# logoi_smd_gndpln_v0_1.net
KiCad netlist of a schematic drawn in EAGLE
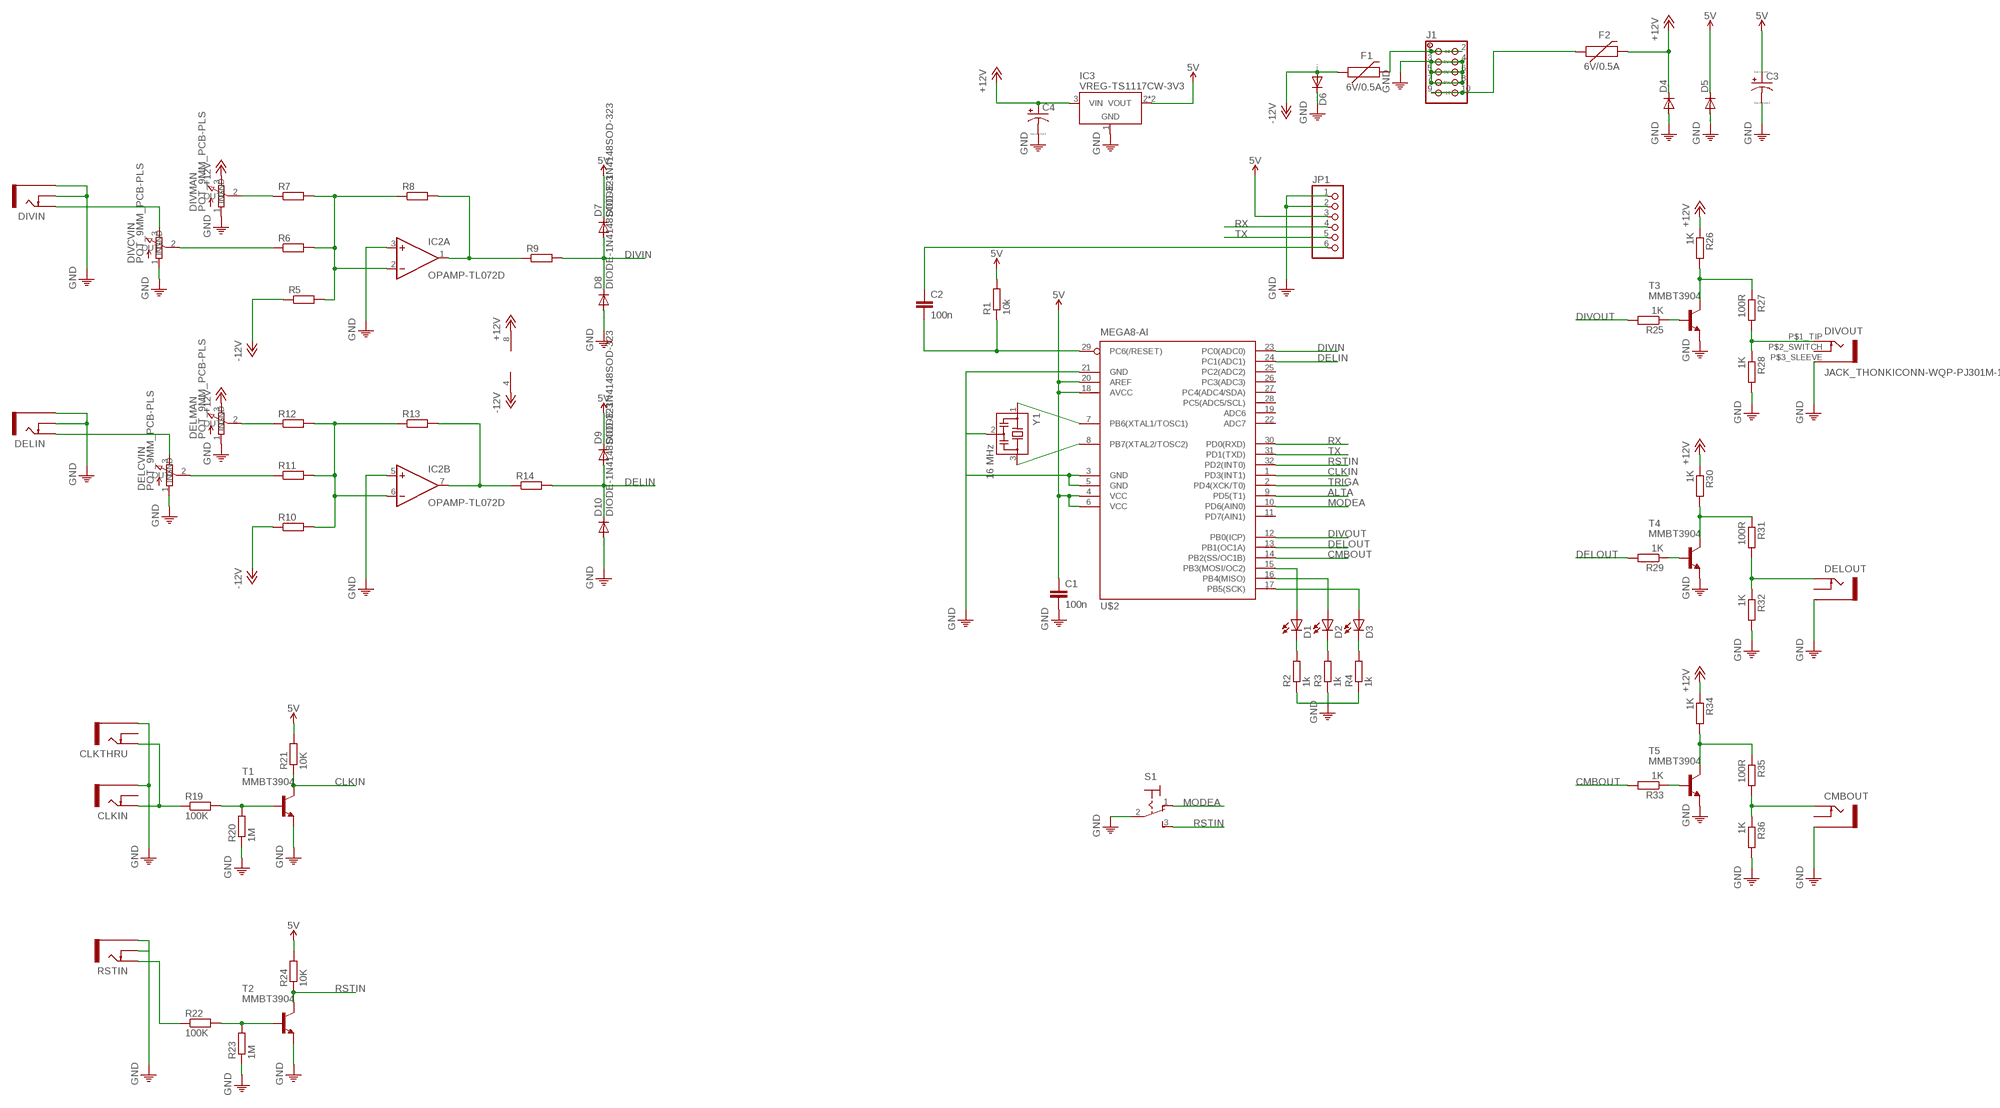
[diagram p0: schematic, sheet 1]

(export (version "E")
  (design (tool "Eeschema 10.0.6"))
  (components
    (comp (ref "C1")
      (value "100n")
      (footprint "eagle-import:C0603K")
      (libsource (lib "eagle-import") (part "CAPACITOR-EUC0603K"))
    )
    (comp (ref "C2")
      (value "100n")
      (footprint "eagle-import:C0603K")
      (libsource (lib "eagle-import") (part "CAPACITOR-EUC0603K"))
    )
    (comp (ref "C3")
      (value "CAPACITOR_POLARIZED-USE2.5-5")
      (footprint "eagle-import:E2,5-5")
      (libsource (lib "eagle-import") (part "CAPACITOR_POLARIZED-USE2.5-5"))
    )
    (comp (ref "C4")
      (value "CAPACITOR_POLARIZED-USE2.5-5")
      (footprint "eagle-import:E2,5-5")
      (libsource (lib "eagle-import") (part "CAPACITOR_POLARIZED-USE2.5-5"))
    )
    (comp (ref "CLKIN")
      (value "JACK_THONKICONNNEW")
      (footprint "eagle-import:WQP-PJ301M-12_JACK")
      (libsource (lib "eagle-import") (part "JACK_THONKICONNNEW"))
    )
    (comp (ref "CLKTHRU")
      (value "JACK_THONKICONNNEW")
      (footprint "eagle-import:WQP-PJ301M-12_JACK")
      (libsource (lib "eagle-import") (part "JACK_THONKICONNNEW"))
    )
    (comp (ref "CMBOUT")
      (value "JACK_THONKICONNNEW")
      (footprint "eagle-import:WQP-PJ301M-12_JACK")
      (libsource (lib "eagle-import") (part "JACK_THONKICONNNEW"))
    )
    (comp (ref "D1")
      (value "LED3MM")
      (footprint "eagle-import:LED3MM")
      (libsource (lib "eagle-import") (part "LED3MM"))
    )
    (comp (ref "D2")
      (value "LED3MM")
      (footprint "eagle-import:LED3MM")
      (libsource (lib "eagle-import") (part "LED3MM"))
    )
    (comp (ref "D3")
      (value "LED3MM")
      (footprint "eagle-import:LED3MM")
      (libsource (lib "eagle-import") (part "LED3MM"))
    )
    (comp (ref "D4")
      (value "DIODE-DO-214AC")
      (footprint "eagle-import:DO-214AC")
      (libsource (lib "eagle-import") (part "DIODE-DO-214AC"))
    )
    (comp (ref "D5")
      (value "DIODE-DO-214AC")
      (footprint "eagle-import:DO-214AC")
      (libsource (lib "eagle-import") (part "DIODE-DO-214AC"))
    )
    (comp (ref "D6")
      (value "DIODE-DO-214AC")
      (footprint "eagle-import:DO-214AC")
      (libsource (lib "eagle-import") (part "DIODE-DO-214AC"))
    )
    (comp (ref "D7")
      (value "DIODE-1N4148SOD-323")
      (footprint "eagle-import:SOD323W_INFINEON")
      (libsource (lib "eagle-import") (part "DIODE-1N4148SOD-323"))
    )
    (comp (ref "D8")
      (value "DIODE-1N4148SOD-323")
      (footprint "eagle-import:SOD323W_INFINEON")
      (libsource (lib "eagle-import") (part "DIODE-1N4148SOD-323"))
    )
    (comp (ref "D9")
      (value "DIODE-1N4148SOD-323")
      (footprint "eagle-import:SOD323W_INFINEON")
      (libsource (lib "eagle-import") (part "DIODE-1N4148SOD-323"))
    )
    (comp (ref "D10")
      (value "DIODE-1N4148SOD-323")
      (footprint "eagle-import:SOD323W_INFINEON")
      (libsource (lib "eagle-import") (part "DIODE-1N4148SOD-323"))
    )
    (comp (ref "DELCVIN")
      (value "POT_9MM_PCB-PLS")
      (footprint "eagle-import:9MM_PLS")
      (libsource (lib "eagle-import") (part "POT_9MM_PCB-PLS"))
    )
    (comp (ref "DELIN")
      (value "JACK_THONKICONNNEW")
      (footprint "eagle-import:WQP-PJ301M-12_JACK")
      (libsource (lib "eagle-import") (part "JACK_THONKICONNNEW"))
    )
    (comp (ref "DELMAN")
      (value "POT_9MM_PCB-PLS")
      (footprint "eagle-import:9MM_PLS")
      (libsource (lib "eagle-import") (part "POT_9MM_PCB-PLS"))
    )
    (comp (ref "DELOUT")
      (value "JACK_THONKICONNNEW")
      (footprint "eagle-import:WQP-PJ301M-12_JACK")
      (libsource (lib "eagle-import") (part "JACK_THONKICONNNEW"))
    )
    (comp (ref "DIVCVIN")
      (value "POT_9MM_PCB-PLS")
      (footprint "eagle-import:9MM_PLS")
      (libsource (lib "eagle-import") (part "POT_9MM_PCB-PLS"))
    )
    (comp (ref "DIVIN")
      (value "JACK_THONKICONNNEW")
      (footprint "eagle-import:WQP-PJ301M-12_JACK")
      (libsource (lib "eagle-import") (part "JACK_THONKICONNNEW"))
    )
    (comp (ref "DIVMAN")
      (value "POT_9MM_PCB-PLS")
      (footprint "eagle-import:9MM_PLS")
      (libsource (lib "eagle-import") (part "POT_9MM_PCB-PLS"))
    )
    (comp (ref "DIVOUT")
      (value "JACK_THONKICONN-WQP-PJ301M-12")
      (footprint "eagle-import:WQP-PJ301M-12_JACK")
      (libsource (lib "eagle-import") (part "JACK_THONKICONN-WQP-PJ301M-12"))
    )
    (comp (ref "F1")
      (value "6V/0.5A")
      (footprint "eagle-import:1206")
      (libsource (lib "eagle-import") (part "FUSE-PPTC_HALF-AMP"))
    )
    (comp (ref "F2")
      (value "6V/0.5A")
      (footprint "eagle-import:1206")
      (libsource (lib "eagle-import") (part "FUSE-PPTC_HALF-AMP"))
    )
    (comp (ref "IC2")
      (value "OPAMP-TL072D")
      (footprint "eagle-import:SO08")
      (libsource (lib "eagle-import") (part "OPAMP-TL072D"))
    )
    (comp (ref "IC3")
      (value "VREG-TS1117CW-3V3")
      (footprint "eagle-import:SOT223")
      (libsource (lib "eagle-import") (part "VREG-TS1117CW-3V3"))
    )
    (comp (ref "J1")
      (value "HEADER-EUROPWR_2X05-OPEN")
      (footprint "eagle-import:2X05_EUROPWR_OPEN")
      (libsource (lib "eagle-import") (part "HEADER-EUROPWR_2X05-OPEN"))
    )
    (comp (ref "JP1")
      (value "PINHD-1X6")
      (footprint "eagle-import:1X06")
      (libsource (lib "eagle-import") (part "PINHD-1X6"))
    )
    (comp (ref "R1")
      (value "10k")
      (footprint "eagle-import:R0603")
      (libsource (lib "eagle-import") (part "RESISTOR-EU_R0603"))
    )
    (comp (ref "R2")
      (value "1k")
      (footprint "eagle-import:R0603")
      (libsource (lib "eagle-import") (part "RESISTOR-EU_R0603"))
    )
    (comp (ref "R3")
      (value "1k")
      (footprint "eagle-import:R0603")
      (libsource (lib "eagle-import") (part "RESISTOR-EU_R0603"))
    )
    (comp (ref "R4")
      (value "1k")
      (footprint "eagle-import:R0603")
      (libsource (lib "eagle-import") (part "RESISTOR-EU_R0603"))
    )
    (comp (ref "R5")
      (value "RESISTOR-EU_R0603")
      (footprint "eagle-import:R0603")
      (libsource (lib "eagle-import") (part "RESISTOR-EU_R0603"))
    )
    (comp (ref "R6")
      (value "RESISTOR-EU_R0603")
      (footprint "eagle-import:R0603")
      (libsource (lib "eagle-import") (part "RESISTOR-EU_R0603"))
    )
    (comp (ref "R7")
      (value "RESISTOR-EU_R0603")
      (footprint "eagle-import:R0603")
      (libsource (lib "eagle-import") (part "RESISTOR-EU_R0603"))
    )
    (comp (ref "R8")
      (value "RESISTOR-EU_R0603")
      (footprint "eagle-import:R0603")
      (libsource (lib "eagle-import") (part "RESISTOR-EU_R0603"))
    )
    (comp (ref "R9")
      (value "RESISTOR-EU_R0603")
      (footprint "eagle-import:R0603")
      (libsource (lib "eagle-import") (part "RESISTOR-EU_R0603"))
    )
    (comp (ref "R10")
      (value "RESISTOR-EU_R0603")
      (footprint "eagle-import:R0603")
      (libsource (lib "eagle-import") (part "RESISTOR-EU_R0603"))
    )
    (comp (ref "R11")
      (value "RESISTOR-EU_R0603")
      (footprint "eagle-import:R0603")
      (libsource (lib "eagle-import") (part "RESISTOR-EU_R0603"))
    )
    (comp (ref "R12")
      (value "RESISTOR-EU_R0603")
      (footprint "eagle-import:R0603")
      (libsource (lib "eagle-import") (part "RESISTOR-EU_R0603"))
    )
    (comp (ref "R13")
      (value "RESISTOR-EU_R0603")
      (footprint "eagle-import:R0603")
      (libsource (lib "eagle-import") (part "RESISTOR-EU_R0603"))
    )
    (comp (ref "R14")
      (value "RESISTOR-EU_R0603")
      (footprint "eagle-import:R0603")
      (libsource (lib "eagle-import") (part "RESISTOR-EU_R0603"))
    )
    (comp (ref "R19")
      (value "100K")
      (footprint "eagle-import:R0603")
      (libsource (lib "eagle-import") (part "RESISTOR-EU_R0603"))
    )
    (comp (ref "R20")
      (value "1M")
      (footprint "eagle-import:R0603")
      (libsource (lib "eagle-import") (part "RESISTOR-EU_R0603"))
    )
    (comp (ref "R21")
      (value "10K")
      (footprint "eagle-import:R0603")
      (libsource (lib "eagle-import") (part "RESISTOR-EU_R0603"))
    )
    (comp (ref "R22")
      (value "100K")
      (footprint "eagle-import:R0603")
      (libsource (lib "eagle-import") (part "RESISTOR-EU_R0603"))
    )
    (comp (ref "R23")
      (value "1M")
      (footprint "eagle-import:R0603")
      (libsource (lib "eagle-import") (part "RESISTOR-EU_R0603"))
    )
    (comp (ref "R24")
      (value "10K")
      (footprint "eagle-import:R0603")
      (libsource (lib "eagle-import") (part "RESISTOR-EU_R0603"))
    )
    (comp (ref "R25")
      (value "1K")
      (footprint "eagle-import:R0603")
      (libsource (lib "eagle-import") (part "RESISTOR-EU_R0603"))
    )
    (comp (ref "R26")
      (value "1K")
      (footprint "eagle-import:R0603")
      (libsource (lib "eagle-import") (part "RESISTOR-EU_R0603"))
    )
    (comp (ref "R27")
      (value "100R")
      (footprint "eagle-import:R0603")
      (libsource (lib "eagle-import") (part "RESISTOR-EU_R0603"))
    )
    (comp (ref "R28")
      (value "1K")
      (footprint "eagle-import:R0603")
      (libsource (lib "eagle-import") (part "RESISTOR-EU_R0603"))
    )
    (comp (ref "R29")
      (value "1K")
      (footprint "eagle-import:R0603")
      (libsource (lib "eagle-import") (part "RESISTOR-EU_R0603"))
    )
    (comp (ref "R30")
      (value "1K")
      (footprint "eagle-import:R0603")
      (libsource (lib "eagle-import") (part "RESISTOR-EU_R0603"))
    )
    (comp (ref "R31")
      (value "100R")
      (footprint "eagle-import:R0603")
      (libsource (lib "eagle-import") (part "RESISTOR-EU_R0603"))
    )
    (comp (ref "R32")
      (value "1K")
      (footprint "eagle-import:R0603")
      (libsource (lib "eagle-import") (part "RESISTOR-EU_R0603"))
    )
    (comp (ref "R33")
      (value "1K")
      (footprint "eagle-import:R0603")
      (libsource (lib "eagle-import") (part "RESISTOR-EU_R0603"))
    )
    (comp (ref "R34")
      (value "1K")
      (footprint "eagle-import:R0603")
      (libsource (lib "eagle-import") (part "RESISTOR-EU_R0603"))
    )
    (comp (ref "R35")
      (value "100R")
      (footprint "eagle-import:R0603")
      (libsource (lib "eagle-import") (part "RESISTOR-EU_R0603"))
    )
    (comp (ref "R36")
      (value "1K")
      (footprint "eagle-import:R0603")
      (libsource (lib "eagle-import") (part "RESISTOR-EU_R0603"))
    )
    (comp (ref "RSTIN")
      (value "JACK_THONKICONNNEW")
      (footprint "eagle-import:WQP-PJ301M-12_JACK")
      (libsource (lib "eagle-import") (part "JACK_THONKICONNNEW"))
    )
    (comp (ref "S1")
      (value "SWITCH-SPDT-320-916")
      (footprint "eagle-import:320-916")
      (libsource (lib "eagle-import") (part "SWITCH-SPDT-320-916"))
    )
    (comp (ref "T1")
      (value "MMBT3904")
      (footprint "eagle-import:SOT23-BEC")
      (libsource (lib "eagle-import") (part "TRANSISTOR-NPN-SOT23-BECMMBT3904LT1"))
    )
    (comp (ref "T2")
      (value "MMBT3904")
      (footprint "eagle-import:SOT23-BEC")
      (libsource (lib "eagle-import") (part "TRANSISTOR-NPN-SOT23-BECMMBT3904LT1"))
    )
    (comp (ref "T3")
      (value "MMBT3904")
      (footprint "eagle-import:SOT23-BEC")
      (libsource (lib "eagle-import") (part "TRANSISTOR-NPN-SOT23-BECMMBT3904LT1"))
    )
    (comp (ref "T4")
      (value "MMBT3904")
      (footprint "eagle-import:SOT23-BEC")
      (libsource (lib "eagle-import") (part "TRANSISTOR-NPN-SOT23-BECMMBT3904LT1"))
    )
    (comp (ref "T5")
      (value "MMBT3904")
      (footprint "eagle-import:SOT23-BEC")
      (libsource (lib "eagle-import") (part "TRANSISTOR-NPN-SOT23-BECMMBT3904LT1"))
    )
    (comp (ref "U$2")
      (value "MEGA8-AI")
      (footprint "eagle-import:TQFP32-08")
      (fields (field (name "MPN") "ATMEGA8-16AU"))
      (libsource (lib "eagle-import") (part "MEGA8-AI"))
    )
    (comp (ref "Y1")
      (value "16 MHz")
      (footprint "eagle-import:CSTCR6M")
      (fields (field (name "MPN") "CSTCR6M00G53-R0"))
      (libsource (lib "eagle-import") (part "CSTCR6M00G53Z"))
    )
  )
  (nets
    (net (code "1") (name "+12V") (class "Default")
      (node (ref "C4") (pin "+") (pinfunction "+_+") (pintype "passive"))
      (node (ref "D4") (pin "C") (pinfunction "C_C") (pintype "passive"))
      (node (ref "DELMAN") (pin "3") (pinfunction "IN_3") (pintype "passive"))
      (node (ref "DIVMAN") (pin "3") (pinfunction "IN_3") (pintype "passive"))
      (node (ref "F2") (pin "2") (pinfunction "2_2") (pintype "bidirectional"))
      (node (ref "IC2") (pin "8") (pinfunction "V+_8") (pintype "power_in"))
      (node (ref "IC3") (pin "3") (pinfunction "VIN_3") (pintype "power_in"))
      (node (ref "R26") (pin "1") (pinfunction "1_1") (pintype "passive"))
      (node (ref "R30") (pin "1") (pinfunction "1_1") (pintype "passive"))
      (node (ref "R34") (pin "1") (pinfunction "1_1") (pintype "passive"))
    )
    (net (code "2") (name "-12V") (class "Default")
      (node (ref "D6") (pin "A") (pinfunction "A_A") (pintype "passive"))
      (node (ref "F1") (pin "1") (pinfunction "1_1") (pintype "bidirectional"))
      (node (ref "IC2") (pin "4") (pinfunction "V-_4") (pintype "power_in"))
      (node (ref "R10") (pin "1") (pinfunction "1_1") (pintype "passive"))
      (node (ref "R5") (pin "1") (pinfunction "1_1") (pintype "passive"))
    )
    (net (code "3") (name "/ALTA") (class "Default")
      (node (ref "U$2") (pin "9") (pinfunction "PD5(T1)_9") (pintype "bidirectional"))
    )
    (net (code "4") (name "/CLKIN") (class "Default")
      (node (ref "R21") (pin "1") (pinfunction "1_1") (pintype "passive"))
      (node (ref "T1") (pin "C") (pinfunction "C_C") (pintype "passive"))
      (node (ref "U$2") (pin "1") (pinfunction "PD3(INT1)_1") (pintype "bidirectional"))
    )
    (net (code "5") (name "/CMBOUT") (class "Default")
      (node (ref "R33") (pin "2") (pinfunction "2_2") (pintype "passive"))
      (node (ref "U$2") (pin "14") (pinfunction "PB2(SS/OC1B)_14") (pintype "bidirectional"))
    )
    (net (code "6") (name "/DELIN") (class "Default")
      (node (ref "D10") (pin "C") (pinfunction "C_C") (pintype "passive"))
      (node (ref "D9") (pin "A") (pinfunction "A_A") (pintype "passive"))
      (node (ref "R14") (pin "2") (pinfunction "2_2") (pintype "passive"))
      (node (ref "U$2") (pin "24") (pinfunction "PC1(ADC1)_24") (pintype "bidirectional"))
    )
    (net (code "7") (name "/DELOUT") (class "Default")
      (node (ref "R29") (pin "2") (pinfunction "2_2") (pintype "passive"))
      (node (ref "U$2") (pin "13") (pinfunction "PB1(OC1A)_13") (pintype "bidirectional"))
    )
    (net (code "8") (name "/DIVIN") (class "Default")
      (node (ref "D7") (pin "A") (pinfunction "A_A") (pintype "passive"))
      (node (ref "D8") (pin "C") (pinfunction "C_C") (pintype "passive"))
      (node (ref "R9") (pin "2") (pinfunction "2_2") (pintype "passive"))
      (node (ref "U$2") (pin "23") (pinfunction "PC0(ADC0)_23") (pintype "bidirectional"))
    )
    (net (code "9") (name "/DIVOUT") (class "Default")
      (node (ref "R25") (pin "2") (pinfunction "2_2") (pintype "passive"))
      (node (ref "U$2") (pin "12") (pinfunction "PB0(ICP)_12") (pintype "bidirectional"))
    )
    (net (code "10") (name "/MODEA") (class "Default")
      (node (ref "S1") (pin "1") (pinfunction "O_1") (pintype "passive"))
      (node (ref "U$2") (pin "10") (pinfunction "PD6(AIN0)_10") (pintype "bidirectional"))
    )
    (net (code "11") (name "/RSTIN") (class "Default")
      (node (ref "R24") (pin "1") (pinfunction "1_1") (pintype "passive"))
      (node (ref "S1") (pin "3") (pinfunction "S_3") (pintype "passive"))
      (node (ref "T2") (pin "C") (pinfunction "C_C") (pintype "passive"))
      (node (ref "U$2") (pin "32") (pinfunction "PD2(INT0)_32") (pintype "bidirectional"))
    )
    (net (code "12") (name "/RX") (class "Default")
      (node (ref "JP1") (pin "4") (pinfunction "4_4") (pintype "passive"))
      (node (ref "U$2") (pin "30") (pinfunction "PD0(RXD)_30") (pintype "bidirectional"))
    )
    (net (code "13") (name "/TRIGA") (class "Default")
      (node (ref "U$2") (pin "2") (pinfunction "PD4(XCK/T0)_2") (pintype "bidirectional"))
    )
    (net (code "14") (name "/TX") (class "Default")
      (node (ref "JP1") (pin "5") (pinfunction "5_5") (pintype "passive"))
      (node (ref "U$2") (pin "31") (pinfunction "PD1(TXD)_31") (pintype "bidirectional"))
    )
    (net (code "15") (name "5V") (class "Default")
      (node (ref "C1") (pin "1") (pinfunction "1_1") (pintype "passive"))
      (node (ref "C3") (pin "+") (pinfunction "+_+") (pintype "passive"))
      (node (ref "D5") (pin "C") (pinfunction "C_C") (pintype "passive"))
      (node (ref "D7") (pin "C") (pinfunction "C_C") (pintype "passive"))
      (node (ref "D9") (pin "C") (pinfunction "C_C") (pintype "passive"))
      (node (ref "IC3") (pin "2") (pinfunction "VOUT_2") (pintype "power_in"))
      (node (ref "IC3") (pin "4") (pinfunction "VOUT_4") (pintype "power_in"))
      (node (ref "JP1") (pin "3") (pinfunction "3_3") (pintype "passive"))
      (node (ref "R1") (pin "2") (pinfunction "2_2") (pintype "passive"))
      (node (ref "R21") (pin "2") (pinfunction "2_2") (pintype "passive"))
      (node (ref "R24") (pin "2") (pinfunction "2_2") (pintype "passive"))
      (node (ref "U$2") (pin "18") (pinfunction "AVCC_18") (pintype "power_in"))
      (node (ref "U$2") (pin "20") (pinfunction "AREF_20") (pintype "passive"))
      (node (ref "U$2") (pin "4") (pinfunction "VCC_4") (pintype "power_in"))
      (node (ref "U$2") (pin "6") (pinfunction "VCC_6") (pintype "power_in"))
    )
    (net (code "16") (name "GND") (class "Default")
      (node (ref "C1") (pin "2") (pinfunction "2_2") (pintype "passive"))
      (node (ref "C3") (pin "-") (pinfunction "-_-") (pintype "passive"))
      (node (ref "C4") (pin "-") (pinfunction "-_-") (pintype "passive"))
      (node (ref "CLKIN") (pin "P$3_SLEEVE") (pinfunction "SLEEVE_P$3_SLEEVE") (pintype "passive"))
      (node (ref "CLKTHRU") (pin "P$3_SLEEVE") (pinfunction "SLEEVE_P$3_SLEEVE") (pintype "passive"))
      (node (ref "CMBOUT") (pin "P$3_SLEEVE") (pinfunction "SLEEVE_P$3_SLEEVE") (pintype "passive"))
      (node (ref "D10") (pin "A") (pinfunction "A_A") (pintype "passive"))
      (node (ref "D4") (pin "A") (pinfunction "A_A") (pintype "passive"))
      (node (ref "D5") (pin "A") (pinfunction "A_A") (pintype "passive"))
      (node (ref "D6") (pin "C") (pinfunction "C_C") (pintype "passive"))
      (node (ref "D8") (pin "A") (pinfunction "A_A") (pintype "passive"))
      (node (ref "DELCVIN") (pin "1") (pinfunction "GND_1") (pintype "passive"))
      (node (ref "DELIN") (pin "P$2_SWITCH") (pinfunction "SWITCH_P$2_SWITCH") (pintype "passive"))
      (node (ref "DELIN") (pin "P$3_SLEEVE") (pinfunction "SLEEVE_P$3_SLEEVE") (pintype "passive"))
      (node (ref "DELMAN") (pin "1") (pinfunction "GND_1") (pintype "passive"))
      (node (ref "DELOUT") (pin "P$3_SLEEVE") (pinfunction "SLEEVE_P$3_SLEEVE") (pintype "passive"))
      (node (ref "DIVCVIN") (pin "1") (pinfunction "GND_1") (pintype "passive"))
      (node (ref "DIVIN") (pin "P$2_SWITCH") (pinfunction "SWITCH_P$2_SWITCH") (pintype "passive"))
      (node (ref "DIVIN") (pin "P$3_SLEEVE") (pinfunction "SLEEVE_P$3_SLEEVE") (pintype "passive"))
      (node (ref "DIVMAN") (pin "1") (pinfunction "GND_1") (pintype "passive"))
      (node (ref "DIVOUT") (pin "P$3_SLEEVE") (pinfunction "1_P$3_SLEEVE") (pintype "passive"))
      (node (ref "IC2") (pin "3") (pinfunction "+IN_3") (pintype "input"))
      (node (ref "IC2") (pin "5") (pinfunction "+IN_5") (pintype "input"))
      (node (ref "IC3") (pin "1") (pinfunction "GND_1") (pintype "power_in"))
      (node (ref "J1") (pin "3") (pinfunction "3_3") (pintype "passive"))
      (node (ref "J1") (pin "4") (pinfunction "4_4") (pintype "passive"))
      (node (ref "J1") (pin "5") (pinfunction "5_5") (pintype "passive"))
      (node (ref "J1") (pin "6") (pinfunction "6_6") (pintype "passive"))
      (node (ref "J1") (pin "7") (pinfunction "7_7") (pintype "passive"))
      (node (ref "J1") (pin "8") (pinfunction "8_8") (pintype "passive"))
      (node (ref "JP1") (pin "1") (pinfunction "1_1") (pintype "passive"))
      (node (ref "JP1") (pin "2") (pinfunction "2_2") (pintype "passive"))
      (node (ref "R2") (pin "1") (pinfunction "1_1") (pintype "passive"))
      (node (ref "R20") (pin "1") (pinfunction "1_1") (pintype "passive"))
      (node (ref "R23") (pin "1") (pinfunction "1_1") (pintype "passive"))
      (node (ref "R28") (pin "2") (pinfunction "2_2") (pintype "passive"))
      (node (ref "R3") (pin "1") (pinfunction "1_1") (pintype "passive"))
      (node (ref "R32") (pin "2") (pinfunction "2_2") (pintype "passive"))
      (node (ref "R36") (pin "2") (pinfunction "2_2") (pintype "passive"))
      (node (ref "R4") (pin "1") (pinfunction "1_1") (pintype "passive"))
      (node (ref "RSTIN") (pin "P$2_SWITCH") (pinfunction "SWITCH_P$2_SWITCH") (pintype "passive"))
      (node (ref "RSTIN") (pin "P$3_SLEEVE") (pinfunction "SLEEVE_P$3_SLEEVE") (pintype "passive"))
      (node (ref "S1") (pin "2") (pinfunction "P_2") (pintype "passive"))
      (node (ref "T1") (pin "E") (pinfunction "E_E") (pintype "passive"))
      (node (ref "T2") (pin "E") (pinfunction "E_E") (pintype "passive"))
      (node (ref "T3") (pin "E") (pinfunction "E_E") (pintype "passive"))
      (node (ref "T4") (pin "E") (pinfunction "E_E") (pintype "passive"))
      (node (ref "T5") (pin "E") (pinfunction "E_E") (pintype "passive"))
      (node (ref "U$2") (pin "21") (pinfunction "GND_21") (pintype "power_in"))
      (node (ref "U$2") (pin "3") (pinfunction "GND_3") (pintype "power_in"))
      (node (ref "U$2") (pin "5") (pinfunction "GND_5") (pintype "power_in"))
      (node (ref "Y1") (pin "2") (pinfunction "2_2") (pintype "passive"))
    )
    (net (code "17") (name "Net-(C2-Pad1)") (class "Default")
      (node (ref "C2") (pin "1") (pinfunction "1_1") (pintype "passive"))
      (node (ref "JP1") (pin "6") (pinfunction "6_6") (pintype "passive"))
    )
    (net (code "18") (name "Net-(CLKIN-TIP)") (class "Default")
      (node (ref "CLKIN") (pin "P$1_TIP") (pinfunction "TIP_P$1_TIP") (pintype "passive"))
      (node (ref "CLKTHRU") (pin "P$1_TIP") (pinfunction "TIP_P$1_TIP") (pintype "passive"))
      (node (ref "R19") (pin "1") (pinfunction "1_1") (pintype "passive"))
    )
    (net (code "19") (name "Net-(CMBOUT-TIP)") (class "Default")
      (node (ref "CMBOUT") (pin "P$1_TIP") (pinfunction "TIP_P$1_TIP") (pintype "passive"))
      (node (ref "R35") (pin "2") (pinfunction "2_2") (pintype "passive"))
      (node (ref "R36") (pin "1") (pinfunction "1_1") (pintype "passive"))
    )
    (net (code "20") (name "Net-(D1-C)") (class "Default")
      (node (ref "D1") (pin "K") (pinfunction "C_K") (pintype "passive"))
      (node (ref "R2") (pin "2") (pinfunction "2_2") (pintype "passive"))
    )
    (net (code "21") (name "Net-(D2-C)") (class "Default")
      (node (ref "D2") (pin "K") (pinfunction "C_K") (pintype "passive"))
      (node (ref "R3") (pin "2") (pinfunction "2_2") (pintype "passive"))
    )
    (net (code "22") (name "Net-(D3-C)") (class "Default")
      (node (ref "D3") (pin "K") (pinfunction "C_K") (pintype "passive"))
      (node (ref "R4") (pin "2") (pinfunction "2_2") (pintype "passive"))
    )
    (net (code "23") (name "Net-(DELCVIN-IN)") (class "Default")
      (node (ref "DELCVIN") (pin "3") (pinfunction "IN_3") (pintype "passive"))
      (node (ref "DELIN") (pin "P$1_TIP") (pinfunction "TIP_P$1_TIP") (pintype "passive"))
    )
    (net (code "24") (name "Net-(DELCVIN-OUT)") (class "Default")
      (node (ref "DELCVIN") (pin "2") (pinfunction "OUT_2") (pintype "passive"))
      (node (ref "R11") (pin "1") (pinfunction "1_1") (pintype "passive"))
    )
    (net (code "25") (name "Net-(DELMAN-OUT)") (class "Default")
      (node (ref "DELMAN") (pin "2") (pinfunction "OUT_2") (pintype "passive"))
      (node (ref "R12") (pin "1") (pinfunction "1_1") (pintype "passive"))
    )
    (net (code "26") (name "Net-(DELOUT-TIP)") (class "Default")
      (node (ref "DELOUT") (pin "P$1_TIP") (pinfunction "TIP_P$1_TIP") (pintype "passive"))
      (node (ref "R31") (pin "2") (pinfunction "2_2") (pintype "passive"))
      (node (ref "R32") (pin "1") (pinfunction "1_1") (pintype "passive"))
    )
    (net (code "27") (name "Net-(DIVCVIN-IN)") (class "Default")
      (node (ref "DIVCVIN") (pin "3") (pinfunction "IN_3") (pintype "passive"))
      (node (ref "DIVIN") (pin "P$1_TIP") (pinfunction "TIP_P$1_TIP") (pintype "passive"))
    )
    (net (code "28") (name "Net-(DIVCVIN-OUT)") (class "Default")
      (node (ref "DIVCVIN") (pin "2") (pinfunction "OUT_2") (pintype "passive"))
      (node (ref "R6") (pin "1") (pinfunction "1_1") (pintype "passive"))
    )
    (net (code "29") (name "Net-(DIVMAN-OUT)") (class "Default")
      (node (ref "DIVMAN") (pin "2") (pinfunction "OUT_2") (pintype "passive"))
      (node (ref "R7") (pin "1") (pinfunction "1_1") (pintype "passive"))
    )
    (net (code "30") (name "Net-(DIVOUT-2)") (class "Default")
      (node (ref "DIVOUT") (pin "P$1_TIP") (pinfunction "2_P$1_TIP") (pintype "passive"))
      (node (ref "R27") (pin "2") (pinfunction "2_2") (pintype "passive"))
      (node (ref "R28") (pin "1") (pinfunction "1_1") (pintype "passive"))
    )
    (net (code "31") (name "Net-(F1-Pad2)") (class "Default")
      (node (ref "F1") (pin "2") (pinfunction "2_2") (pintype "bidirectional"))
      (node (ref "J1") (pin "1") (pinfunction "1_1") (pintype "passive"))
      (node (ref "J1") (pin "2") (pinfunction "2_2") (pintype "passive"))
    )
    (net (code "32") (name "Net-(F2-Pad1)") (class "Default")
      (node (ref "F2") (pin "1") (pinfunction "1_1") (pintype "bidirectional"))
      (node (ref "J1") (pin "10") (pinfunction "10_10") (pintype "passive"))
      (node (ref "J1") (pin "9") (pinfunction "9_9") (pintype "passive"))
    )
    (net (code "33") (name "Net-(IC2A--IN)") (class "Default")
      (node (ref "IC2") (pin "2") (pinfunction "-IN_2") (pintype "input"))
      (node (ref "R5") (pin "2") (pinfunction "2_2") (pintype "passive"))
      (node (ref "R6") (pin "2") (pinfunction "2_2") (pintype "passive"))
      (node (ref "R7") (pin "2") (pinfunction "2_2") (pintype "passive"))
      (node (ref "R8") (pin "1") (pinfunction "1_1") (pintype "passive"))
    )
    (net (code "34") (name "Net-(IC2A-OUT)") (class "Default")
      (node (ref "IC2") (pin "1") (pinfunction "OUT_1") (pintype "output"))
      (node (ref "R8") (pin "2") (pinfunction "2_2") (pintype "passive"))
      (node (ref "R9") (pin "1") (pinfunction "1_1") (pintype "passive"))
    )
    (net (code "35") (name "Net-(IC2B--IN)") (class "Default")
      (node (ref "IC2") (pin "6") (pinfunction "-IN_6") (pintype "input"))
      (node (ref "R10") (pin "2") (pinfunction "2_2") (pintype "passive"))
      (node (ref "R11") (pin "2") (pinfunction "2_2") (pintype "passive"))
      (node (ref "R12") (pin "2") (pinfunction "2_2") (pintype "passive"))
      (node (ref "R13") (pin "1") (pinfunction "1_1") (pintype "passive"))
    )
    (net (code "36") (name "Net-(IC2B-OUT)") (class "Default")
      (node (ref "IC2") (pin "7") (pinfunction "OUT_7") (pintype "output"))
      (node (ref "R13") (pin "2") (pinfunction "2_2") (pintype "passive"))
      (node (ref "R14") (pin "1") (pinfunction "1_1") (pintype "passive"))
    )
    (net (code "37") (name "Net-(R19-Pad2)") (class "Default")
      (node (ref "R19") (pin "2") (pinfunction "2_2") (pintype "passive"))
      (node (ref "R20") (pin "2") (pinfunction "2_2") (pintype "passive"))
      (node (ref "T1") (pin "B") (pinfunction "B_B") (pintype "passive"))
    )
    (net (code "38") (name "Net-(R22-Pad2)") (class "Default")
      (node (ref "R22") (pin "2") (pinfunction "2_2") (pintype "passive"))
      (node (ref "R23") (pin "2") (pinfunction "2_2") (pintype "passive"))
      (node (ref "T2") (pin "B") (pinfunction "B_B") (pintype "passive"))
    )
    (net (code "39") (name "Net-(R25-Pad1)") (class "Default")
      (node (ref "R25") (pin "1") (pinfunction "1_1") (pintype "passive"))
      (node (ref "T3") (pin "B") (pinfunction "B_B") (pintype "passive"))
    )
    (net (code "40") (name "Net-(R26-Pad2)") (class "Default")
      (node (ref "R26") (pin "2") (pinfunction "2_2") (pintype "passive"))
      (node (ref "R27") (pin "1") (pinfunction "1_1") (pintype "passive"))
      (node (ref "T3") (pin "C") (pinfunction "C_C") (pintype "passive"))
    )
    (net (code "41") (name "Net-(R29-Pad1)") (class "Default")
      (node (ref "R29") (pin "1") (pinfunction "1_1") (pintype "passive"))
      (node (ref "T4") (pin "B") (pinfunction "B_B") (pintype "passive"))
    )
    (net (code "42") (name "Net-(R30-Pad2)") (class "Default")
      (node (ref "R30") (pin "2") (pinfunction "2_2") (pintype "passive"))
      (node (ref "R31") (pin "1") (pinfunction "1_1") (pintype "passive"))
      (node (ref "T4") (pin "C") (pinfunction "C_C") (pintype "passive"))
    )
    (net (code "43") (name "Net-(R33-Pad1)") (class "Default")
      (node (ref "R33") (pin "1") (pinfunction "1_1") (pintype "passive"))
      (node (ref "T5") (pin "B") (pinfunction "B_B") (pintype "passive"))
    )
    (net (code "44") (name "Net-(R34-Pad2)") (class "Default")
      (node (ref "R34") (pin "2") (pinfunction "2_2") (pintype "passive"))
      (node (ref "R35") (pin "1") (pinfunction "1_1") (pintype "passive"))
      (node (ref "T5") (pin "C") (pinfunction "C_C") (pintype "passive"))
    )
    (net (code "45") (name "Net-(RSTIN-TIP)") (class "Default")
      (node (ref "R22") (pin "1") (pinfunction "1_1") (pintype "passive"))
      (node (ref "RSTIN") (pin "P$1_TIP") (pinfunction "TIP_P$1_TIP") (pintype "passive"))
    )
    (net (code "46") (name "Net-(U$2-PB3(MOSI{slash}OC2))") (class "Default")
      (node (ref "D1") (pin "A") (pinfunction "A_A") (pintype "passive"))
      (node (ref "U$2") (pin "15") (pinfunction "PB3(MOSI/OC2)_15") (pintype "bidirectional"))
    )
    (net (code "47") (name "Net-(U$2-PB4(MISO))") (class "Default")
      (node (ref "D2") (pin "A") (pinfunction "A_A") (pintype "passive"))
      (node (ref "U$2") (pin "16") (pinfunction "PB4(MISO)_16") (pintype "bidirectional"))
    )
    (net (code "48") (name "Net-(U$2-PB5(SCK))") (class "Default")
      (node (ref "D3") (pin "A") (pinfunction "A_A") (pintype "passive"))
      (node (ref "U$2") (pin "17") (pinfunction "PB5(SCK)_17") (pintype "bidirectional"))
    )
    (net (code "49") (name "Net-(U$2-PB6(XTAL1{slash}TOSC1))") (class "Default")
      (node (ref "U$2") (pin "7") (pinfunction "PB6(XTAL1/TOSC1)_7") (pintype "bidirectional"))
      (node (ref "Y1") (pin "1") (pinfunction "1_1") (pintype "passive"))
    )
    (net (code "50") (name "Net-(U$2-PB7(XTAL2{slash}TOSC2))") (class "Default")
      (node (ref "U$2") (pin "8") (pinfunction "PB7(XTAL2/TOSC2)_8") (pintype "bidirectional"))
      (node (ref "Y1") (pin "3") (pinfunction "3_3") (pintype "passive"))
    )
    (net (code "51") (name "Net-(U$2-PC6({slash}RESET))") (class "Default")
      (node (ref "C2") (pin "2") (pinfunction "2_2") (pintype "passive"))
      (node (ref "R1") (pin "1") (pinfunction "1_1") (pintype "passive"))
      (node (ref "U$2") (pin "29") (pinfunction "PC6(/RESET)_29") (pintype "bidirectional"))
    )
    (net (code "52") (name "unconnected-(CLKIN-SWITCH-PadP$2_SWITCH)") (class "Default")
      (node (ref "CLKIN") (pin "P$2_SWITCH") (pinfunction "SWITCH_P$2_SWITCH") (pintype "passive"))
    )
    (net (code "53") (name "unconnected-(CLKTHRU-SWITCH-PadP$2_SWITCH)") (class "Default")
      (node (ref "CLKTHRU") (pin "P$2_SWITCH") (pinfunction "SWITCH_P$2_SWITCH") (pintype "passive"))
    )
    (net (code "54") (name "unconnected-(CMBOUT-SWITCH-PadP$2_SWITCH)") (class "Default")
      (node (ref "CMBOUT") (pin "P$2_SWITCH") (pinfunction "SWITCH_P$2_SWITCH") (pintype "passive"))
    )
    (net (code "55") (name "unconnected-(DELOUT-SWITCH-PadP$2_SWITCH)") (class "Default")
      (node (ref "DELOUT") (pin "P$2_SWITCH") (pinfunction "SWITCH_P$2_SWITCH") (pintype "passive"))
    )
    (net (code "56") (name "unconnected-(DIVOUT-3-PadP$2_SWITCH)") (class "Default")
      (node (ref "DIVOUT") (pin "P$2_SWITCH") (pinfunction "3_P$2_SWITCH") (pintype "passive"))
    )
    (net (code "57") (name "unconnected-(U$2-ADC6-Pad19)") (class "Default")
      (node (ref "U$2") (pin "19") (pinfunction "ADC6_19") (pintype "bidirectional"))
    )
    (net (code "58") (name "unconnected-(U$2-ADC7-Pad22)") (class "Default")
      (node (ref "U$2") (pin "22") (pinfunction "ADC7_22") (pintype "bidirectional"))
    )
    (net (code "59") (name "unconnected-(U$2-PC2(ADC2)-Pad25)") (class "Default")
      (node (ref "U$2") (pin "25") (pinfunction "PC2(ADC2)_25") (pintype "bidirectional"))
    )
    (net (code "60") (name "unconnected-(U$2-PC3(ADC3)-Pad26)") (class "Default")
      (node (ref "U$2") (pin "26") (pinfunction "PC3(ADC3)_26") (pintype "bidirectional"))
    )
    (net (code "61") (name "unconnected-(U$2-PC4(ADC4{slash}SDA)-Pad27)") (class "Default")
      (node (ref "U$2") (pin "27") (pinfunction "PC4(ADC4/SDA)_27") (pintype "bidirectional"))
    )
    (net (code "62") (name "unconnected-(U$2-PC5(ADC5{slash}SCL)-Pad28)") (class "Default")
      (node (ref "U$2") (pin "28") (pinfunction "PC5(ADC5/SCL)_28") (pintype "bidirectional"))
    )
    (net (code "63") (name "unconnected-(U$2-PD7(AIN1)-Pad11)") (class "Default")
      (node (ref "U$2") (pin "11") (pinfunction "PD7(AIN1)_11") (pintype "bidirectional"))
    )
  )
)
